# MXC_1_0.net
KiCad netlist of a schematic drawn in EAGLE
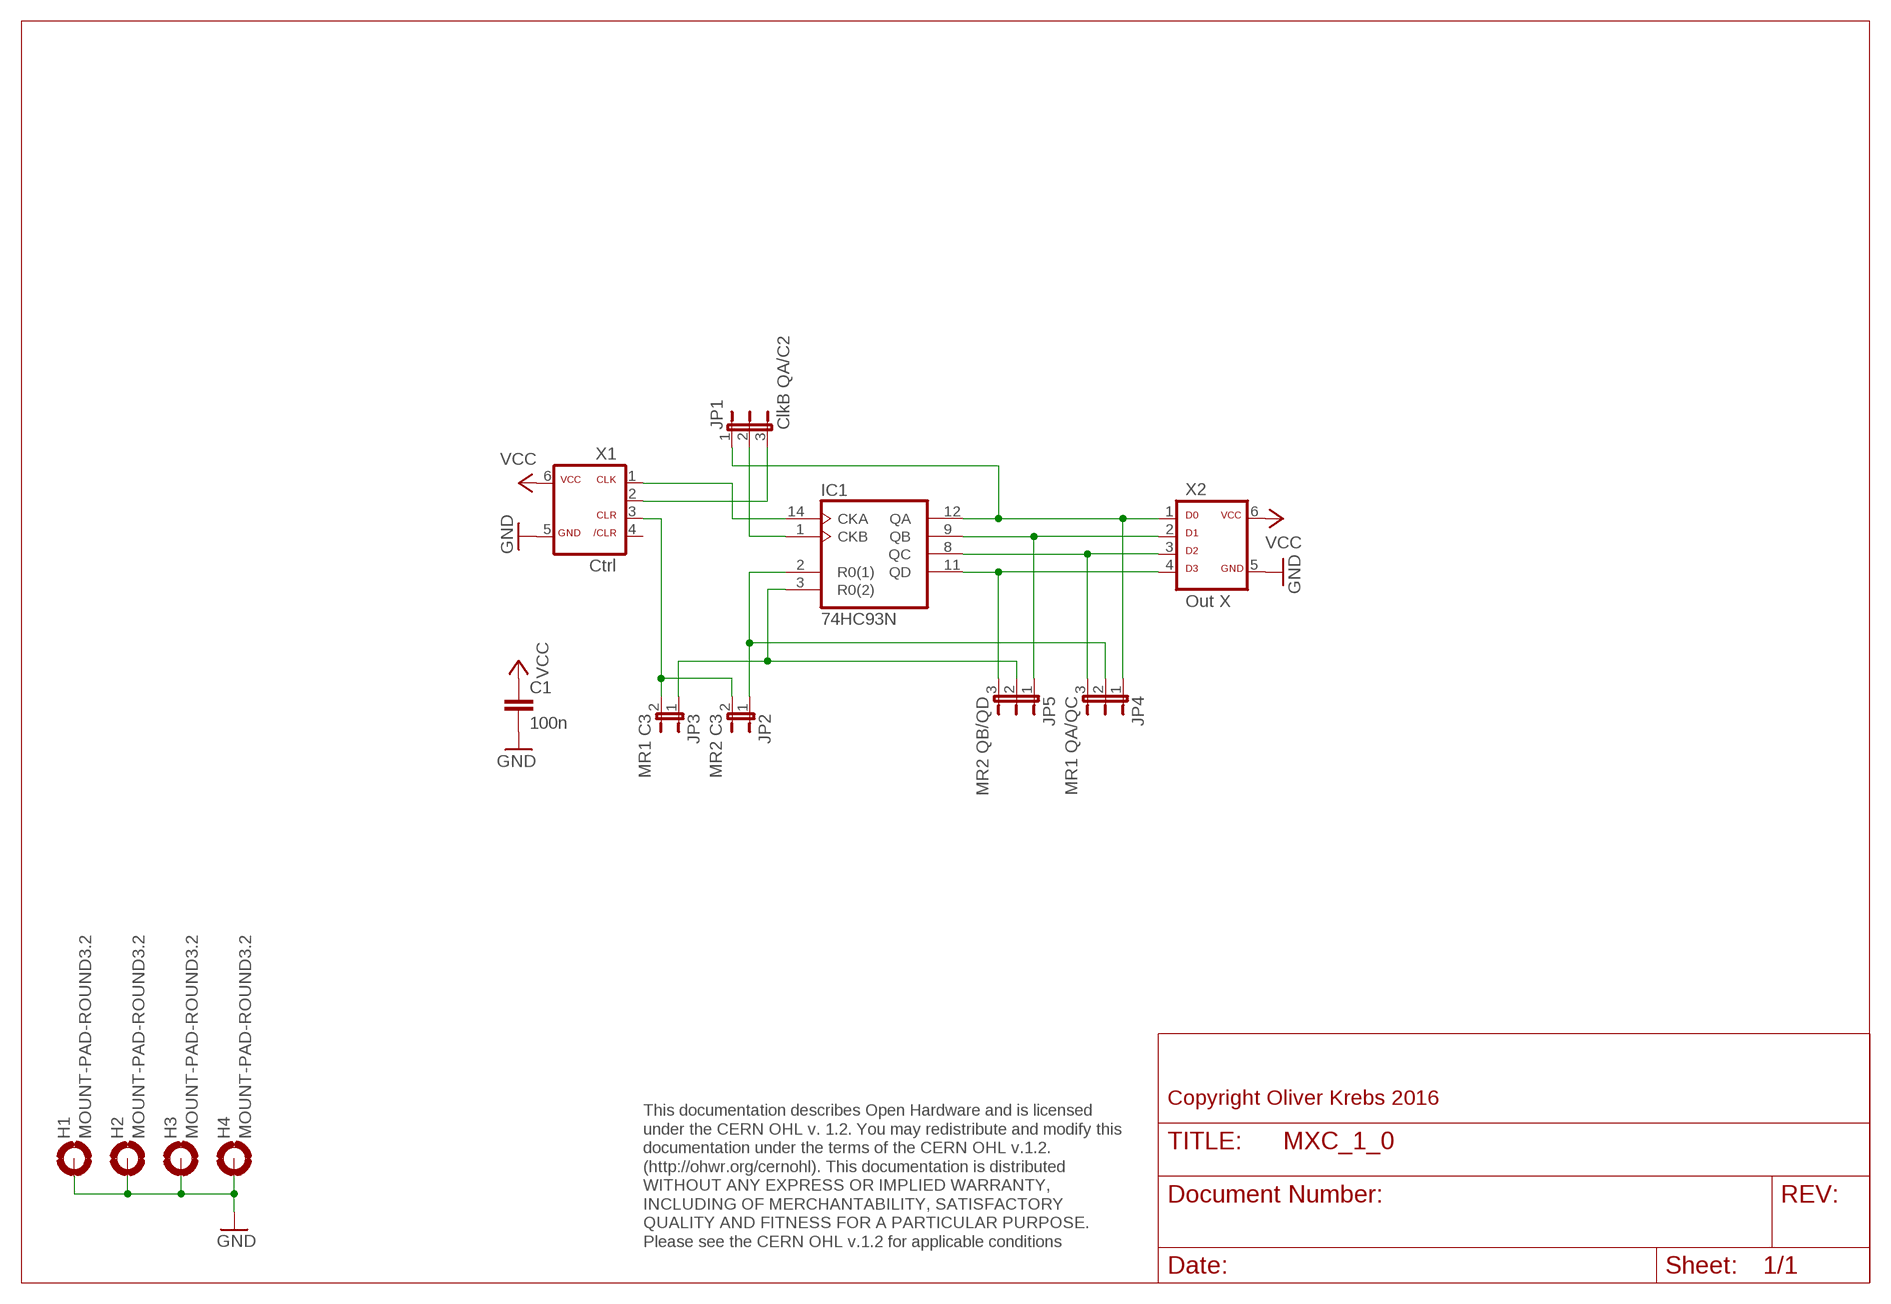
[diagram p0: schematic, sheet 1]

(export (version "E")
  (design (tool "Eeschema 10.0.6"))
  (components
    (comp (ref "C1")
      (value "100n")
      (footprint "eagle-import:C050-025X075")
      (libsource (lib "eagle-import") (part "C-EU050-025X075"))
    )
    (comp (ref "H1")
      (value "MOUNT-PAD-ROUND3.2")
      (footprint "eagle-import:3,2-PAD")
      (libsource (lib "eagle-import") (part "MOUNT-PAD-ROUND3.2"))
    )
    (comp (ref "H2")
      (value "MOUNT-PAD-ROUND3.2")
      (footprint "eagle-import:3,2-PAD")
      (libsource (lib "eagle-import") (part "MOUNT-PAD-ROUND3.2"))
    )
    (comp (ref "H3")
      (value "MOUNT-PAD-ROUND3.2")
      (footprint "eagle-import:3,2-PAD")
      (libsource (lib "eagle-import") (part "MOUNT-PAD-ROUND3.2"))
    )
    (comp (ref "H4")
      (value "MOUNT-PAD-ROUND3.2")
      (footprint "eagle-import:3,2-PAD")
      (libsource (lib "eagle-import") (part "MOUNT-PAD-ROUND3.2"))
    )
    (comp (ref "IC1")
      (value "74HC93N")
      (footprint "eagle-import:DIL14")
      (libsource (lib "eagle-import") (part "7493NHC"))
    )
    (comp (ref "JP1")
      (value "ClkB QA/C2")
      (footprint "eagle-import:JP2-U")
      (libsource (lib "eagle-import") (part "JP2EJP2-U"))
    )
    (comp (ref "JP2")
      (value "MR2 C3")
      (footprint "eagle-import:JP1")
      (libsource (lib "eagle-import") (part "JP1E"))
    )
    (comp (ref "JP3")
      (value "MR1 C3")
      (footprint "eagle-import:JP1")
      (libsource (lib "eagle-import") (part "JP1E"))
    )
    (comp (ref "JP4")
      (value "MR1 QA/QC")
      (footprint "eagle-import:JP2-U")
      (libsource (lib "eagle-import") (part "JP2EJP2-U"))
    )
    (comp (ref "JP5")
      (value "MR2 QB/QD")
      (footprint "eagle-import:JP2-U")
      (libsource (lib "eagle-import") (part "JP2EJP2-U"))
    )
    (comp (ref "X1")
      (value "Ctrl")
      (footprint "eagle-import:ML-6")
      (libsource (lib "eagle-import") (part "ML6C"))
    )
    (comp (ref "X2")
      (value "Out X")
      (footprint "eagle-import:ML-6")
      (libsource (lib "eagle-import") (part "ML6D"))
    )
  )
  (nets
    (net (code "1") (name "GND") (class "Default")
      (node (ref "C1") (pin "2") (pinfunction "2_2") (pintype "passive"))
      (node (ref "H1") (pin "B3,2") (pinfunction "MOUNT_B3,2") (pintype "passive"))
      (node (ref "H2") (pin "B3,2") (pinfunction "MOUNT_B3,2") (pintype "passive"))
      (node (ref "H3") (pin "B3,2") (pinfunction "MOUNT_B3,2") (pintype "passive"))
      (node (ref "H4") (pin "B3,2") (pinfunction "MOUNT_B3,2") (pintype "passive"))
      (node (ref "X1") (pin "5") (pinfunction "5_5") (pintype "passive"))
      (node (ref "X2") (pin "5") (pinfunction "5_5") (pintype "passive"))
    )
    (net (code "2") (name "Net-(IC1A-CKA)") (class "Default")
      (node (ref "IC1") (pin "14") (pinfunction "CKA_14") (pintype "input"))
      (node (ref "X1") (pin "1") (pinfunction "1_1") (pintype "passive"))
    )
    (net (code "3") (name "Net-(IC1A-CKB)") (class "Default")
      (node (ref "IC1") (pin "1") (pinfunction "CKB_1") (pintype "input"))
      (node (ref "JP1") (pin "2") (pinfunction "2_2") (pintype "passive"))
    )
    (net (code "4") (name "Net-(IC1A-QA)") (class "Default")
      (node (ref "IC1") (pin "12") (pinfunction "QA_12") (pintype "output"))
      (node (ref "JP1") (pin "1") (pinfunction "1_1") (pintype "passive"))
      (node (ref "JP4") (pin "1") (pinfunction "1_1") (pintype "passive"))
      (node (ref "X2") (pin "1") (pinfunction "1_1") (pintype "passive"))
    )
    (net (code "5") (name "Net-(IC1A-QB)") (class "Default")
      (node (ref "IC1") (pin "9") (pinfunction "QB_9") (pintype "output"))
      (node (ref "JP5") (pin "1") (pinfunction "1_1") (pintype "passive"))
      (node (ref "X2") (pin "2") (pinfunction "2_2") (pintype "passive"))
    )
    (net (code "6") (name "Net-(IC1A-QC)") (class "Default")
      (node (ref "IC1") (pin "8") (pinfunction "QC_8") (pintype "output"))
      (node (ref "JP4") (pin "3") (pinfunction "3_3") (pintype "passive"))
      (node (ref "X2") (pin "3") (pinfunction "3_3") (pintype "passive"))
    )
    (net (code "7") (name "Net-(IC1A-QD)") (class "Default")
      (node (ref "IC1") (pin "11") (pinfunction "QD_11") (pintype "output"))
      (node (ref "JP5") (pin "3") (pinfunction "3_3") (pintype "passive"))
      (node (ref "X2") (pin "4") (pinfunction "4_4") (pintype "passive"))
    )
    (net (code "8") (name "Net-(IC1A-R0(1))") (class "Default")
      (node (ref "IC1") (pin "2") (pinfunction "R0(1)_2") (pintype "input"))
      (node (ref "JP2") (pin "1") (pinfunction "1_1") (pintype "passive"))
      (node (ref "JP4") (pin "2") (pinfunction "2_2") (pintype "passive"))
    )
    (net (code "9") (name "Net-(IC1A-R0(2))") (class "Default")
      (node (ref "IC1") (pin "3") (pinfunction "R0(2)_3") (pintype "input"))
      (node (ref "JP3") (pin "1") (pinfunction "1_1") (pintype "passive"))
      (node (ref "JP5") (pin "2") (pinfunction "2_2") (pintype "passive"))
    )
    (net (code "10") (name "Net-(JP1-Pad3)") (class "Default")
      (node (ref "JP1") (pin "3") (pinfunction "3_3") (pintype "passive"))
      (node (ref "X1") (pin "2") (pinfunction "2_2") (pintype "passive"))
    )
    (net (code "11") (name "Net-(JP2-Pad2)") (class "Default")
      (node (ref "JP2") (pin "2") (pinfunction "2_2") (pintype "passive"))
      (node (ref "JP3") (pin "2") (pinfunction "2_2") (pintype "passive"))
      (node (ref "X1") (pin "3") (pinfunction "3_3") (pintype "passive"))
    )
    (net (code "12") (name "VCC") (class "Default")
      (node (ref "C1") (pin "1") (pinfunction "1_1") (pintype "passive"))
      (node (ref "X1") (pin "6") (pinfunction "6_6") (pintype "passive"))
      (node (ref "X2") (pin "6") (pinfunction "6_6") (pintype "passive"))
    )
    (net (code "13") (name "unconnected-(X1-Pad4)") (class "Default")
      (node (ref "X1") (pin "4") (pinfunction "4_4") (pintype "passive"))
    )
  )
)
